# PIC32_circuit.net
KiCad netlist of a schematic drawn in EAGLE
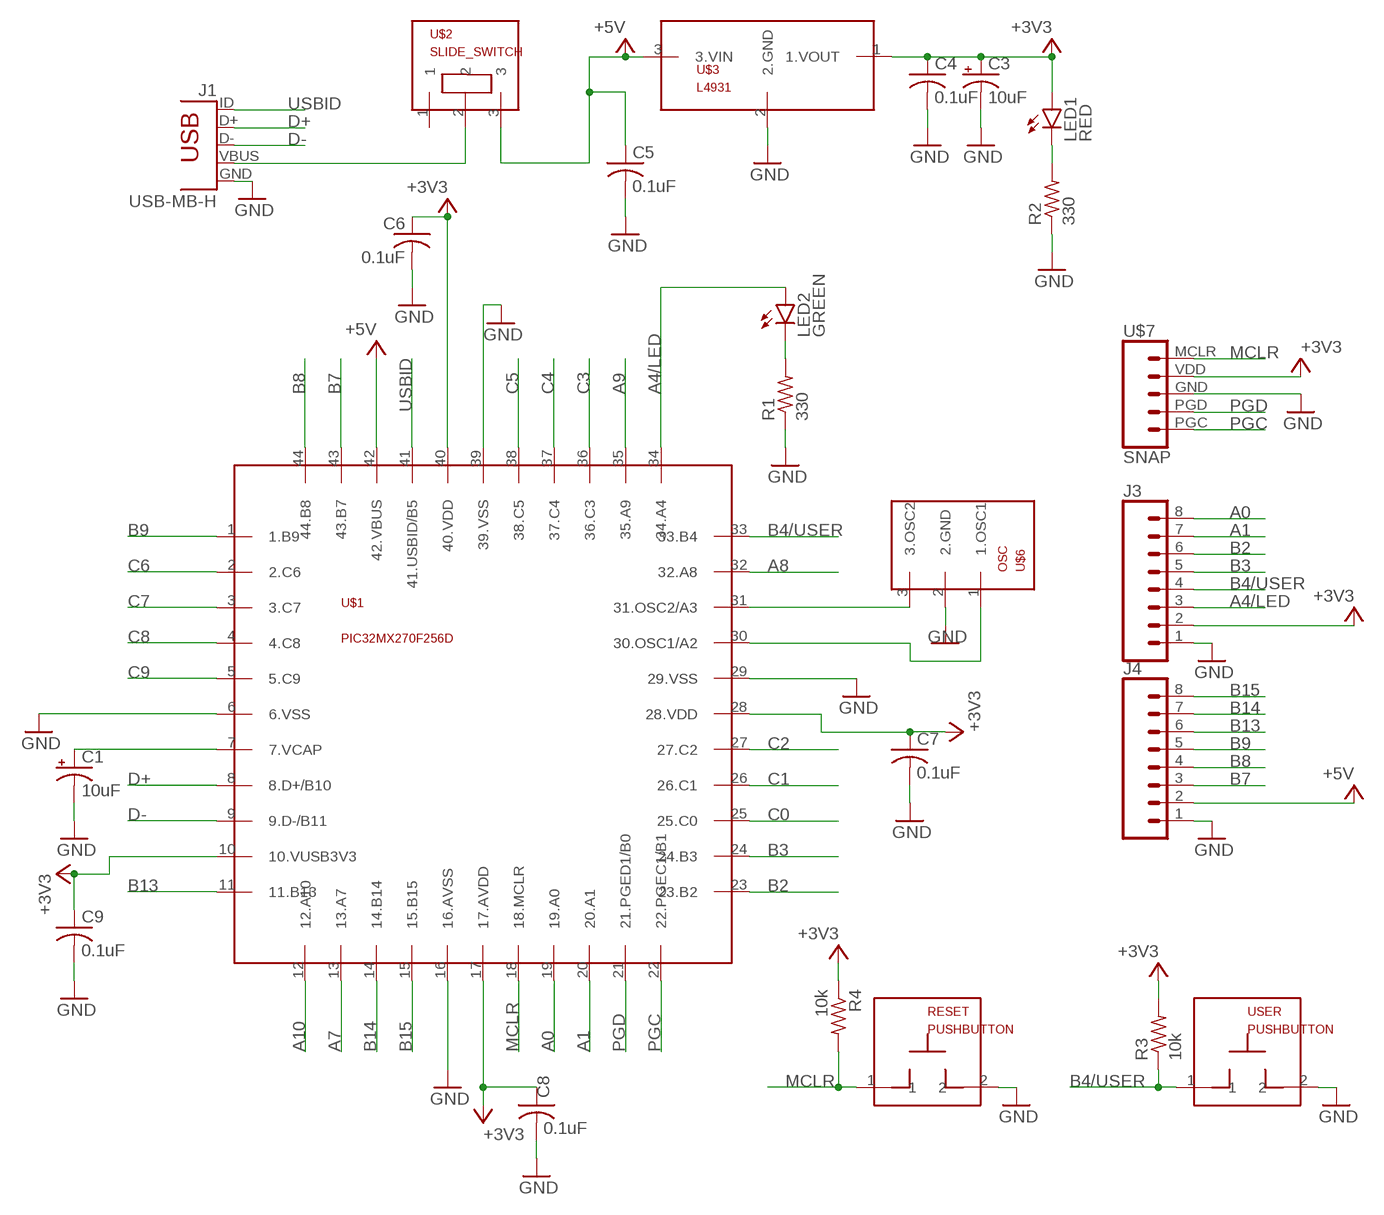
[diagram p0: schematic, sheet 1]

(export (version "E")
  (design (tool "Eeschema 10.0.6"))
  (components
    (comp (ref "C1")
      (value "10uF")
      (footprint "eagle-import:B45181B")
      (libsource (lib "eagle-import") (part "CPOL-USB45181B"))
    )
    (comp (ref "C3")
      (value "10uF")
      (footprint "eagle-import:B45181B")
      (libsource (lib "eagle-import") (part "CPOL-USB45181B"))
    )
    (comp (ref "C4")
      (value "0.1uF")
      (footprint "eagle-import:C025-025X050")
      (libsource (lib "eagle-import") (part "C-US025-025X050"))
    )
    (comp (ref "C5")
      (value "0.1uF")
      (footprint "eagle-import:C025-025X050")
      (libsource (lib "eagle-import") (part "C-US025-025X050"))
    )
    (comp (ref "C6")
      (value "0.1uF")
      (footprint "eagle-import:C025-025X050")
      (libsource (lib "eagle-import") (part "C-US025-025X050"))
    )
    (comp (ref "C7")
      (value "0.1uF")
      (footprint "eagle-import:C025-025X050")
      (libsource (lib "eagle-import") (part "C-US025-025X050"))
    )
    (comp (ref "C8")
      (value "0.1uF")
      (footprint "eagle-import:C025-025X050")
      (libsource (lib "eagle-import") (part "C-US025-025X050"))
    )
    (comp (ref "C9")
      (value "0.1uF")
      (footprint "eagle-import:C025-025X050")
      (libsource (lib "eagle-import") (part "C-US025-025X050"))
    )
    (comp (ref "J1")
      (value "USB-MB-H")
      (footprint "eagle-import:USB-MB-H")
      (libsource (lib "eagle-import") (part "USB-MB-H"))
    )
    (comp (ref "J3")
      (value "CONN_08\"")
      (footprint "eagle-import:1X08")
      (libsource (lib "eagle-import") (part "CONN_08{dblquote}"))
    )
    (comp (ref "J4")
      (value "CONN_08\"")
      (footprint "eagle-import:1X08")
      (libsource (lib "eagle-import") (part "CONN_08{dblquote}"))
    )
    (comp (ref "LED1")
      (value "RED")
      (footprint "eagle-import:LED3MM")
      (fields (field (name "MF") "VISHAY SEMICONDUCTOR"))
      (libsource (lib "eagle-import") (part "TLLR4400"))
    )
    (comp (ref "LED2")
      (value "GREEN")
      (footprint "eagle-import:LED3MM")
      (fields (field (name "MF") "VISHAY SEMICONDUCTOR"))
      (libsource (lib "eagle-import") (part "TLLG4400"))
    )
    (comp (ref "R1")
      (value "330")
      (footprint "eagle-import:0207_10")
      (libsource (lib "eagle-import") (part "R-US_0207/10"))
    )
    (comp (ref "R2")
      (value "330")
      (footprint "eagle-import:0207_10")
      (libsource (lib "eagle-import") (part "R-US_0207/10"))
    )
    (comp (ref "R3")
      (value "10k")
      (footprint "eagle-import:0207_10")
      (libsource (lib "eagle-import") (part "R-US_0207/10"))
    )
    (comp (ref "R4")
      (value "10k")
      (footprint "eagle-import:0207_10")
      (libsource (lib "eagle-import") (part "R-US_0207/10"))
    )
    (comp (ref "RESET")
      (value "PUSHBUTTON")
      (footprint "eagle-import:PUSHBUTTON")
      (libsource (lib "eagle-import") (part "PUSHBUTTON"))
    )
    (comp (ref "U$1")
      (value "PIC32MX270F256D")
      (footprint "eagle-import:TQFP44")
      (libsource (lib "eagle-import") (part "PIC32MX270F256D"))
    )
    (comp (ref "U$2")
      (value "SLIDE_SWITCH")
      (footprint "eagle-import:SLIDE_SWITCH")
      (libsource (lib "eagle-import") (part "SLIDE_SWITCH"))
    )
    (comp (ref "U$3")
      (value "L4931")
      (footprint "eagle-import:TO92-LINE")
      (libsource (lib "eagle-import") (part "L4931"))
    )
    (comp (ref "U$6")
      (value "OSC")
      (footprint "eagle-import:OSC")
      (libsource (lib "eagle-import") (part "OSC"))
    )
    (comp (ref "U$7")
      (value "SNAP")
      (footprint "eagle-import:SNAP")
      (libsource (lib "eagle-import") (part "SNAP"))
    )
    (comp (ref "USER")
      (value "PUSHBUTTON")
      (footprint "eagle-import:PUSHBUTTON")
      (libsource (lib "eagle-import") (part "PUSHBUTTON"))
    )
  )
  (nets
    (net (code "1") (name "+3V3") (class "Default")
      (node (ref "C3") (pin "+") (pinfunction "+_+") (pintype "passive"))
      (node (ref "C4") (pin "1") (pinfunction "1_1") (pintype "passive"))
      (node (ref "C6") (pin "1") (pinfunction "1_1") (pintype "passive"))
      (node (ref "C7") (pin "1") (pinfunction "1_1") (pintype "passive"))
      (node (ref "C8") (pin "1") (pinfunction "1_1") (pintype "passive"))
      (node (ref "C9") (pin "1") (pinfunction "1_1") (pintype "passive"))
      (node (ref "J3") (pin "2") (pinfunction "2_2") (pintype "passive"))
      (node (ref "LED1") (pin "A") (pinfunction "A_A") (pintype "passive"))
      (node (ref "R3") (pin "2") (pinfunction "2_2") (pintype "passive"))
      (node (ref "R4") (pin "1") (pinfunction "1_1") (pintype "passive"))
      (node (ref "U$1") (pin "10") (pinfunction "10.VUSB3V3_10") (pintype "bidirectional"))
      (node (ref "U$1") (pin "17") (pinfunction "17.AVDD_17") (pintype "bidirectional"))
      (node (ref "U$1") (pin "28") (pinfunction "28.VDD_28") (pintype "bidirectional"))
      (node (ref "U$1") (pin "40") (pinfunction "40.VDD_40") (pintype "bidirectional"))
      (node (ref "U$3") (pin "1") (pinfunction "1.VOUT_1") (pintype "bidirectional"))
      (node (ref "U$7") (pin "VDD") (pinfunction "VDD_VDD") (pintype "passive"))
    )
    (net (code "2") (name "+5V") (class "Default")
      (node (ref "C5") (pin "1") (pinfunction "1_1") (pintype "passive"))
      (node (ref "J4") (pin "2") (pinfunction "2_2") (pintype "passive"))
      (node (ref "U$1") (pin "42") (pinfunction "42.VBUS_42") (pintype "bidirectional"))
      (node (ref "U$2") (pin "3") (pinfunction "3_3") (pintype "bidirectional"))
      (node (ref "U$3") (pin "3") (pinfunction "3.VIN_3") (pintype "bidirectional"))
    )
    (net (code "3") (name "/A0") (class "Default")
      (node (ref "J3") (pin "8") (pinfunction "8_8") (pintype "passive"))
      (node (ref "U$1") (pin "19") (pinfunction "19.A0_19") (pintype "bidirectional"))
    )
    (net (code "4") (name "/A1") (class "Default")
      (node (ref "J3") (pin "7") (pinfunction "7_7") (pintype "passive"))
      (node (ref "U$1") (pin "20") (pinfunction "20.A1_20") (pintype "bidirectional"))
    )
    (net (code "5") (name "/A4{slash}LED") (class "Default")
      (node (ref "J3") (pin "3") (pinfunction "3_3") (pintype "passive"))
      (node (ref "LED2") (pin "A") (pinfunction "A_A") (pintype "passive"))
      (node (ref "U$1") (pin "34") (pinfunction "34.A4_34") (pintype "bidirectional"))
    )
    (net (code "6") (name "/A7") (class "Default")
      (node (ref "U$1") (pin "13") (pinfunction "13.A7_13") (pintype "bidirectional"))
    )
    (net (code "7") (name "/A8") (class "Default")
      (node (ref "U$1") (pin "32") (pinfunction "32.A8_32") (pintype "bidirectional"))
    )
    (net (code "8") (name "/A9") (class "Default")
      (node (ref "U$1") (pin "35") (pinfunction "35.A9_35") (pintype "bidirectional"))
    )
    (net (code "9") (name "/A10") (class "Default")
      (node (ref "U$1") (pin "12") (pinfunction "12.A10_12") (pintype "bidirectional"))
    )
    (net (code "10") (name "/B2") (class "Default")
      (node (ref "J3") (pin "6") (pinfunction "6_6") (pintype "passive"))
      (node (ref "U$1") (pin "23") (pinfunction "23.B2_23") (pintype "bidirectional"))
    )
    (net (code "11") (name "/B3") (class "Default")
      (node (ref "J3") (pin "5") (pinfunction "5_5") (pintype "passive"))
      (node (ref "U$1") (pin "24") (pinfunction "24.B3_24") (pintype "bidirectional"))
    )
    (net (code "12") (name "/B4{slash}USER") (class "Default")
      (node (ref "J3") (pin "4") (pinfunction "4_4") (pintype "passive"))
      (node (ref "R3") (pin "1") (pinfunction "1_1") (pintype "passive"))
      (node (ref "U$1") (pin "33") (pinfunction "33.B4_33") (pintype "bidirectional"))
      (node (ref "USER") (pin "1") (pinfunction "1_1") (pintype "bidirectional"))
    )
    (net (code "13") (name "/B7") (class "Default")
      (node (ref "J4") (pin "3") (pinfunction "3_3") (pintype "passive"))
      (node (ref "U$1") (pin "43") (pinfunction "43.B7_43") (pintype "bidirectional"))
    )
    (net (code "14") (name "/B8") (class "Default")
      (node (ref "J4") (pin "4") (pinfunction "4_4") (pintype "passive"))
      (node (ref "U$1") (pin "44") (pinfunction "44.B8_44") (pintype "bidirectional"))
    )
    (net (code "15") (name "/B9") (class "Default")
      (node (ref "J4") (pin "5") (pinfunction "5_5") (pintype "passive"))
      (node (ref "U$1") (pin "1") (pinfunction "1.B9_1") (pintype "bidirectional"))
    )
    (net (code "16") (name "/B13") (class "Default")
      (node (ref "J4") (pin "6") (pinfunction "6_6") (pintype "passive"))
      (node (ref "U$1") (pin "11") (pinfunction "11.B13_11") (pintype "bidirectional"))
    )
    (net (code "17") (name "/B14") (class "Default")
      (node (ref "J4") (pin "7") (pinfunction "7_7") (pintype "passive"))
      (node (ref "U$1") (pin "14") (pinfunction "14.B14_14") (pintype "bidirectional"))
    )
    (net (code "18") (name "/B15") (class "Default")
      (node (ref "J4") (pin "8") (pinfunction "8_8") (pintype "passive"))
      (node (ref "U$1") (pin "15") (pinfunction "15.B15_15") (pintype "bidirectional"))
    )
    (net (code "19") (name "/C0") (class "Default")
      (node (ref "U$1") (pin "25") (pinfunction "25.C0_25") (pintype "bidirectional"))
    )
    (net (code "20") (name "/C1") (class "Default")
      (node (ref "U$1") (pin "26") (pinfunction "26.C1_26") (pintype "bidirectional"))
    )
    (net (code "21") (name "/C2") (class "Default")
      (node (ref "U$1") (pin "27") (pinfunction "27.C2_27") (pintype "bidirectional"))
    )
    (net (code "22") (name "/C3") (class "Default")
      (node (ref "U$1") (pin "36") (pinfunction "36.C3_36") (pintype "bidirectional"))
    )
    (net (code "23") (name "/C4") (class "Default")
      (node (ref "U$1") (pin "37") (pinfunction "37.C4_37") (pintype "bidirectional"))
    )
    (net (code "24") (name "/C5") (class "Default")
      (node (ref "U$1") (pin "38") (pinfunction "38.C5_38") (pintype "bidirectional"))
    )
    (net (code "25") (name "/C6") (class "Default")
      (node (ref "U$1") (pin "2") (pinfunction "2.C6_2") (pintype "bidirectional"))
    )
    (net (code "26") (name "/C7") (class "Default")
      (node (ref "U$1") (pin "3") (pinfunction "3.C7_3") (pintype "bidirectional"))
    )
    (net (code "27") (name "/C8") (class "Default")
      (node (ref "U$1") (pin "4") (pinfunction "4.C8_4") (pintype "bidirectional"))
    )
    (net (code "28") (name "/C9") (class "Default")
      (node (ref "U$1") (pin "5") (pinfunction "5.C9_5") (pintype "bidirectional"))
    )
    (net (code "29") (name "/D+") (class "Default")
      (node (ref "J1") (pin "D+") (pinfunction "D+_D+") (pintype "bidirectional"))
      (node (ref "U$1") (pin "8") (pinfunction "8.D+/B10_8") (pintype "bidirectional"))
    )
    (net (code "30") (name "/D-") (class "Default")
      (node (ref "J1") (pin "D-") (pinfunction "D-_D-") (pintype "bidirectional"))
      (node (ref "U$1") (pin "9") (pinfunction "9.D-/B11_9") (pintype "bidirectional"))
    )
    (net (code "31") (name "/MCLR") (class "Default")
      (node (ref "R4") (pin "2") (pinfunction "2_2") (pintype "passive"))
      (node (ref "RESET") (pin "1") (pinfunction "1_1") (pintype "bidirectional"))
      (node (ref "U$1") (pin "18") (pinfunction "18.MCLR_18") (pintype "bidirectional"))
      (node (ref "U$7") (pin "MCLR") (pinfunction "MCLR_MCLR") (pintype "passive"))
    )
    (net (code "32") (name "/PGC") (class "Default")
      (node (ref "U$1") (pin "22") (pinfunction "22.PGEC1/B1_22") (pintype "bidirectional"))
      (node (ref "U$7") (pin "PGC") (pinfunction "PGC_PGC") (pintype "passive"))
    )
    (net (code "33") (name "/PGD") (class "Default")
      (node (ref "U$1") (pin "21") (pinfunction "21.PGED1/B0_21") (pintype "bidirectional"))
      (node (ref "U$7") (pin "PGD") (pinfunction "PGD_PGD") (pintype "passive"))
    )
    (net (code "34") (name "/USBID") (class "Default")
      (node (ref "J1") (pin "ID") (pinfunction "ID_ID") (pintype "bidirectional"))
      (node (ref "U$1") (pin "41") (pinfunction "41.USBID/B5_41") (pintype "bidirectional"))
    )
    (net (code "35") (name "GND") (class "Default")
      (node (ref "C1") (pin "-") (pinfunction "-_-") (pintype "passive"))
      (node (ref "C3") (pin "-") (pinfunction "-_-") (pintype "passive"))
      (node (ref "C4") (pin "2") (pinfunction "2_2") (pintype "passive"))
      (node (ref "C5") (pin "2") (pinfunction "2_2") (pintype "passive"))
      (node (ref "C6") (pin "2") (pinfunction "2_2") (pintype "passive"))
      (node (ref "C7") (pin "2") (pinfunction "2_2") (pintype "passive"))
      (node (ref "C8") (pin "2") (pinfunction "2_2") (pintype "passive"))
      (node (ref "C9") (pin "2") (pinfunction "2_2") (pintype "passive"))
      (node (ref "J1") (pin "GND") (pinfunction "GND_GND") (pintype "bidirectional"))
      (node (ref "J3") (pin "1") (pinfunction "1_1") (pintype "passive"))
      (node (ref "J4") (pin "1") (pinfunction "1_1") (pintype "passive"))
      (node (ref "R1") (pin "1") (pinfunction "1_1") (pintype "passive"))
      (node (ref "R2") (pin "1") (pinfunction "1_1") (pintype "passive"))
      (node (ref "RESET") (pin "2") (pinfunction "2_2") (pintype "bidirectional"))
      (node (ref "U$1") (pin "16") (pinfunction "16.AVSS_16") (pintype "bidirectional"))
      (node (ref "U$1") (pin "29") (pinfunction "29.VSS_29") (pintype "bidirectional"))
      (node (ref "U$1") (pin "39") (pinfunction "39.VSS_39") (pintype "bidirectional"))
      (node (ref "U$1") (pin "6") (pinfunction "6.VSS_6") (pintype "bidirectional"))
      (node (ref "U$3") (pin "2") (pinfunction "2.GND_2") (pintype "bidirectional"))
      (node (ref "U$6") (pin "2") (pinfunction "2.GND_2") (pintype "bidirectional"))
      (node (ref "U$7") (pin "GND") (pinfunction "GND_GND") (pintype "passive"))
      (node (ref "USER") (pin "2") (pinfunction "2_2") (pintype "bidirectional"))
    )
    (net (code "36") (name "Net-(J1-PadVBUS)") (class "Default")
      (node (ref "J1") (pin "VBUS") (pinfunction "VBUS_VBUS") (pintype "bidirectional"))
      (node (ref "U$2") (pin "2") (pinfunction "2_2") (pintype "bidirectional"))
    )
    (net (code "37") (name "Net-(LED1-C)") (class "Default")
      (node (ref "LED1") (pin "K") (pinfunction "C_K") (pintype "passive"))
      (node (ref "R2") (pin "2") (pinfunction "2_2") (pintype "passive"))
    )
    (net (code "38") (name "Net-(LED2-C)") (class "Default")
      (node (ref "LED2") (pin "K") (pinfunction "C_K") (pintype "passive"))
      (node (ref "R1") (pin "2") (pinfunction "2_2") (pintype "passive"))
    )
    (net (code "39") (name "Net-(U$1-7.VCAP)") (class "Default")
      (node (ref "C1") (pin "+") (pinfunction "+_+") (pintype "passive"))
      (node (ref "U$1") (pin "7") (pinfunction "7.VCAP_7") (pintype "bidirectional"))
    )
    (net (code "40") (name "Net-(U$1-30.OSC1{slash}A2)") (class "Default")
      (node (ref "U$1") (pin "30") (pinfunction "30.OSC1/A2_30") (pintype "bidirectional"))
      (node (ref "U$6") (pin "1") (pinfunction "1.OSC1_1") (pintype "bidirectional"))
    )
    (net (code "41") (name "Net-(U$1-31.OSC2{slash}A3)") (class "Default")
      (node (ref "U$1") (pin "31") (pinfunction "31.OSC2/A3_31") (pintype "bidirectional"))
      (node (ref "U$6") (pin "3") (pinfunction "3.OSC2_3") (pintype "bidirectional"))
    )
    (net (code "42") (name "unconnected-(U$2-Pad1)") (class "Default")
      (node (ref "U$2") (pin "1") (pinfunction "1_1") (pintype "bidirectional"))
    )
  )
)
